# harp_analog_input_v1_0.net
KiCad netlist of a schematic drawn in EAGLE
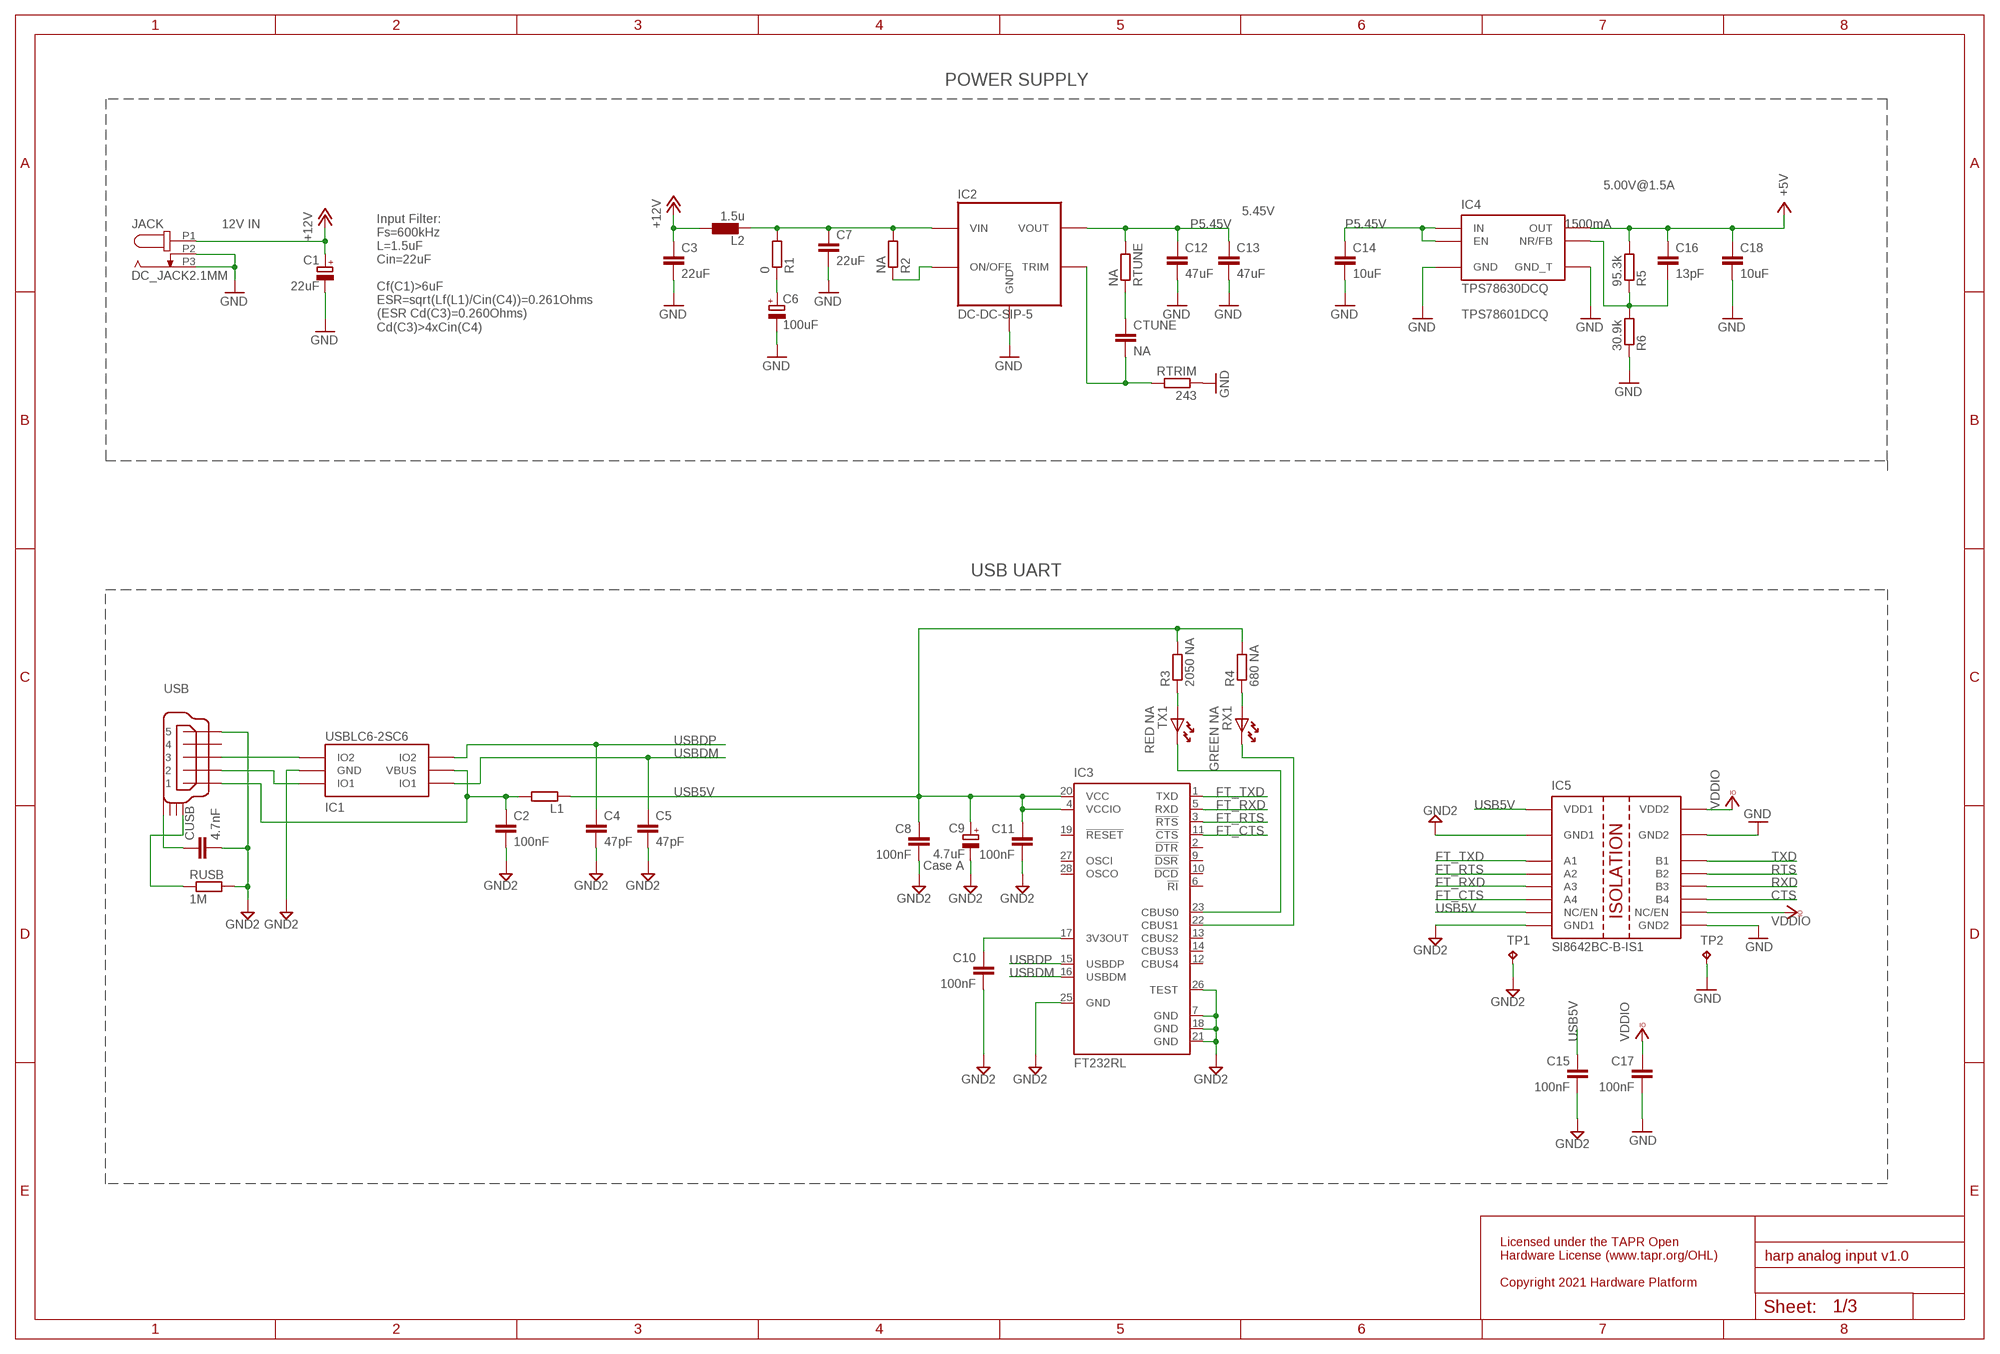
[diagram p0: schematic, sheet 1]
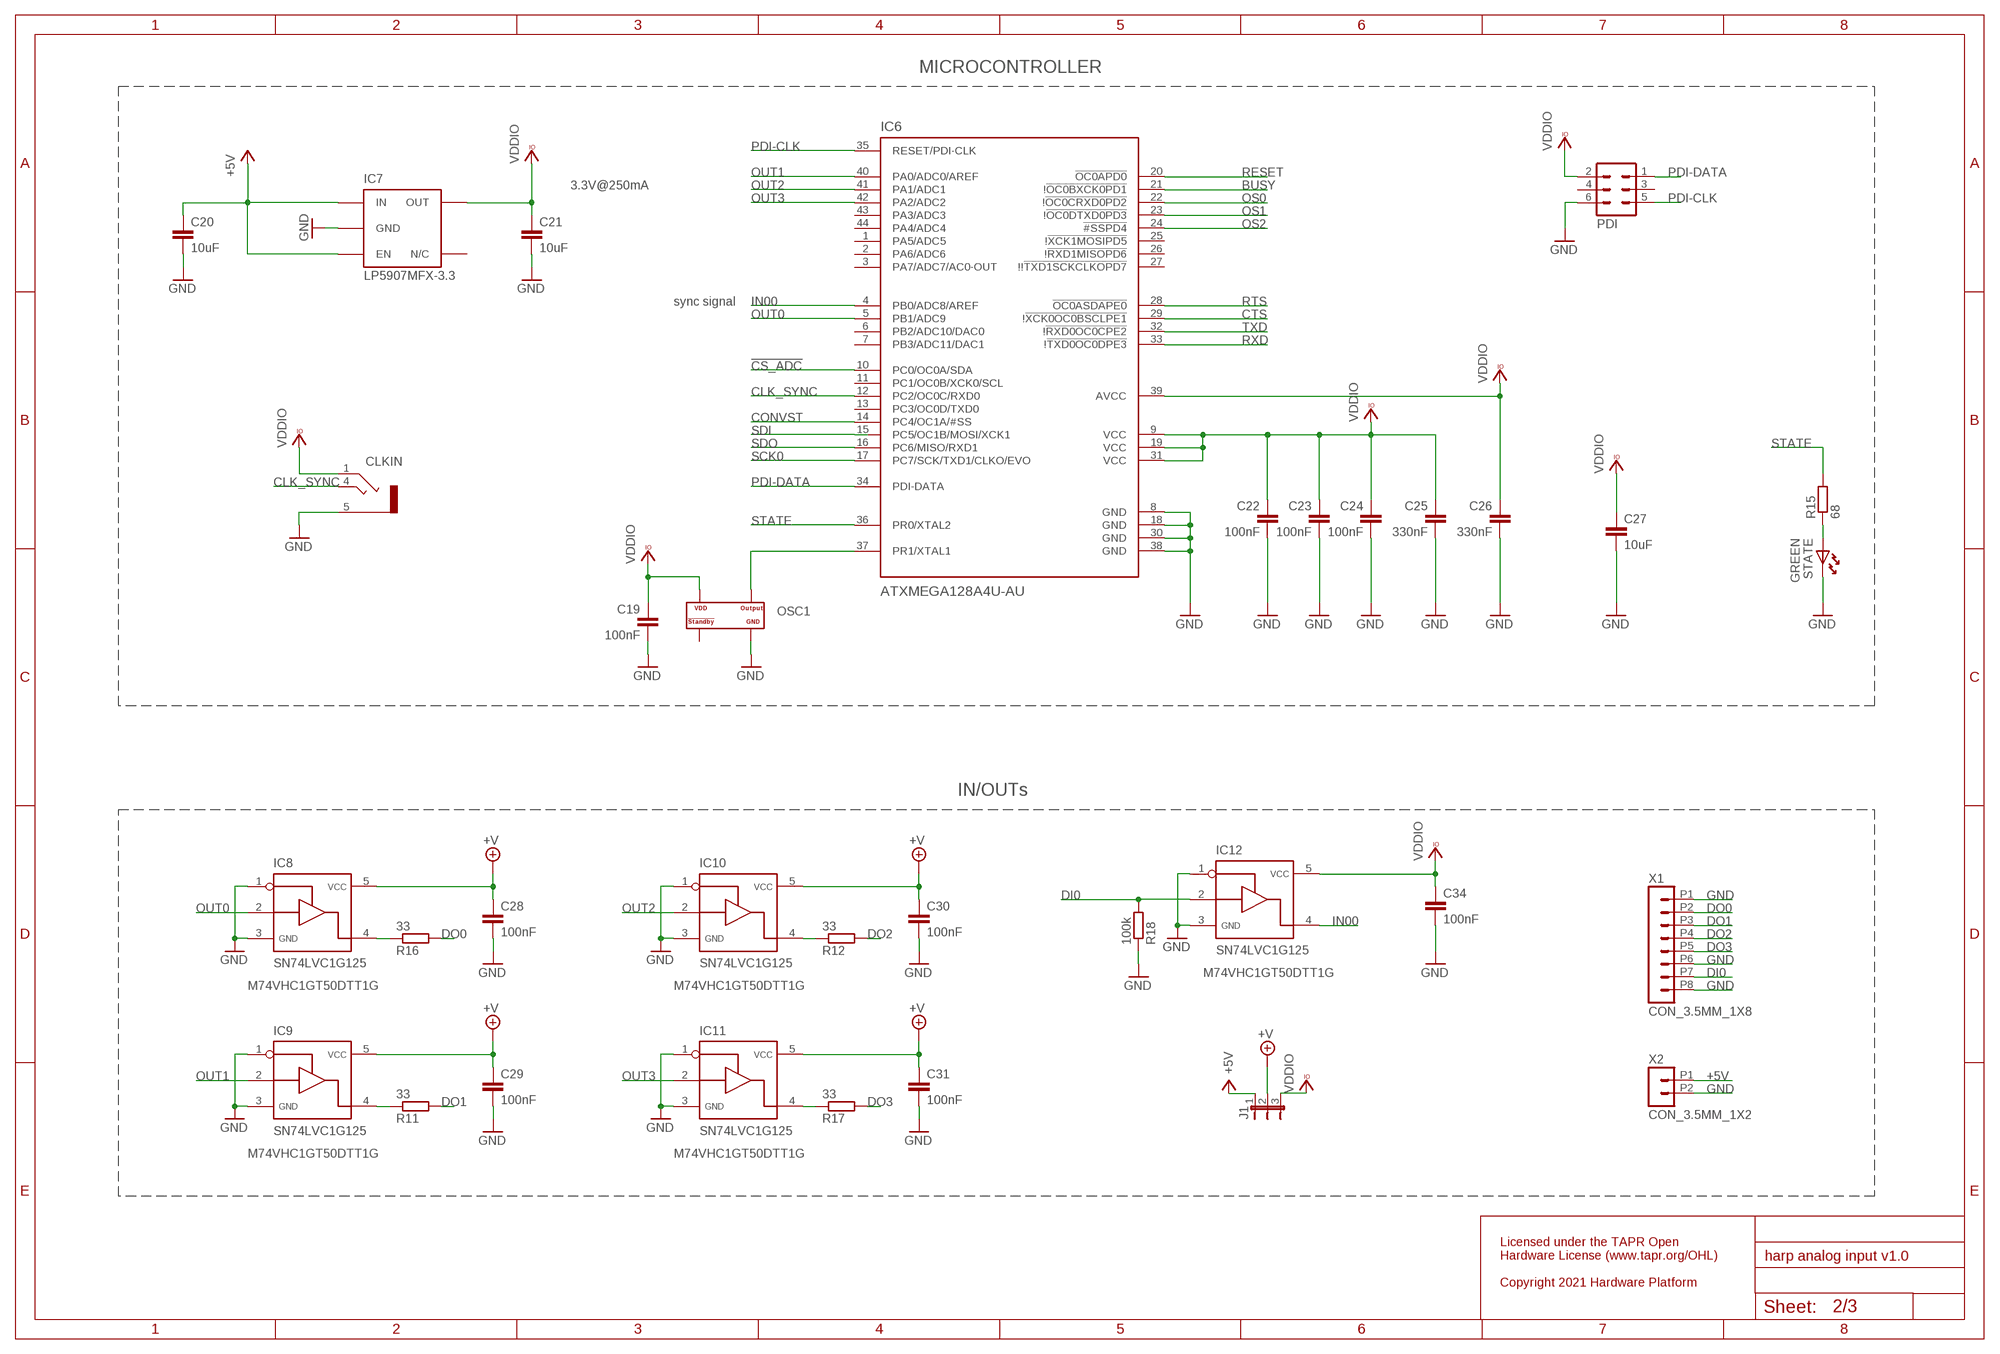
[diagram p1: schematic, sheet 2]
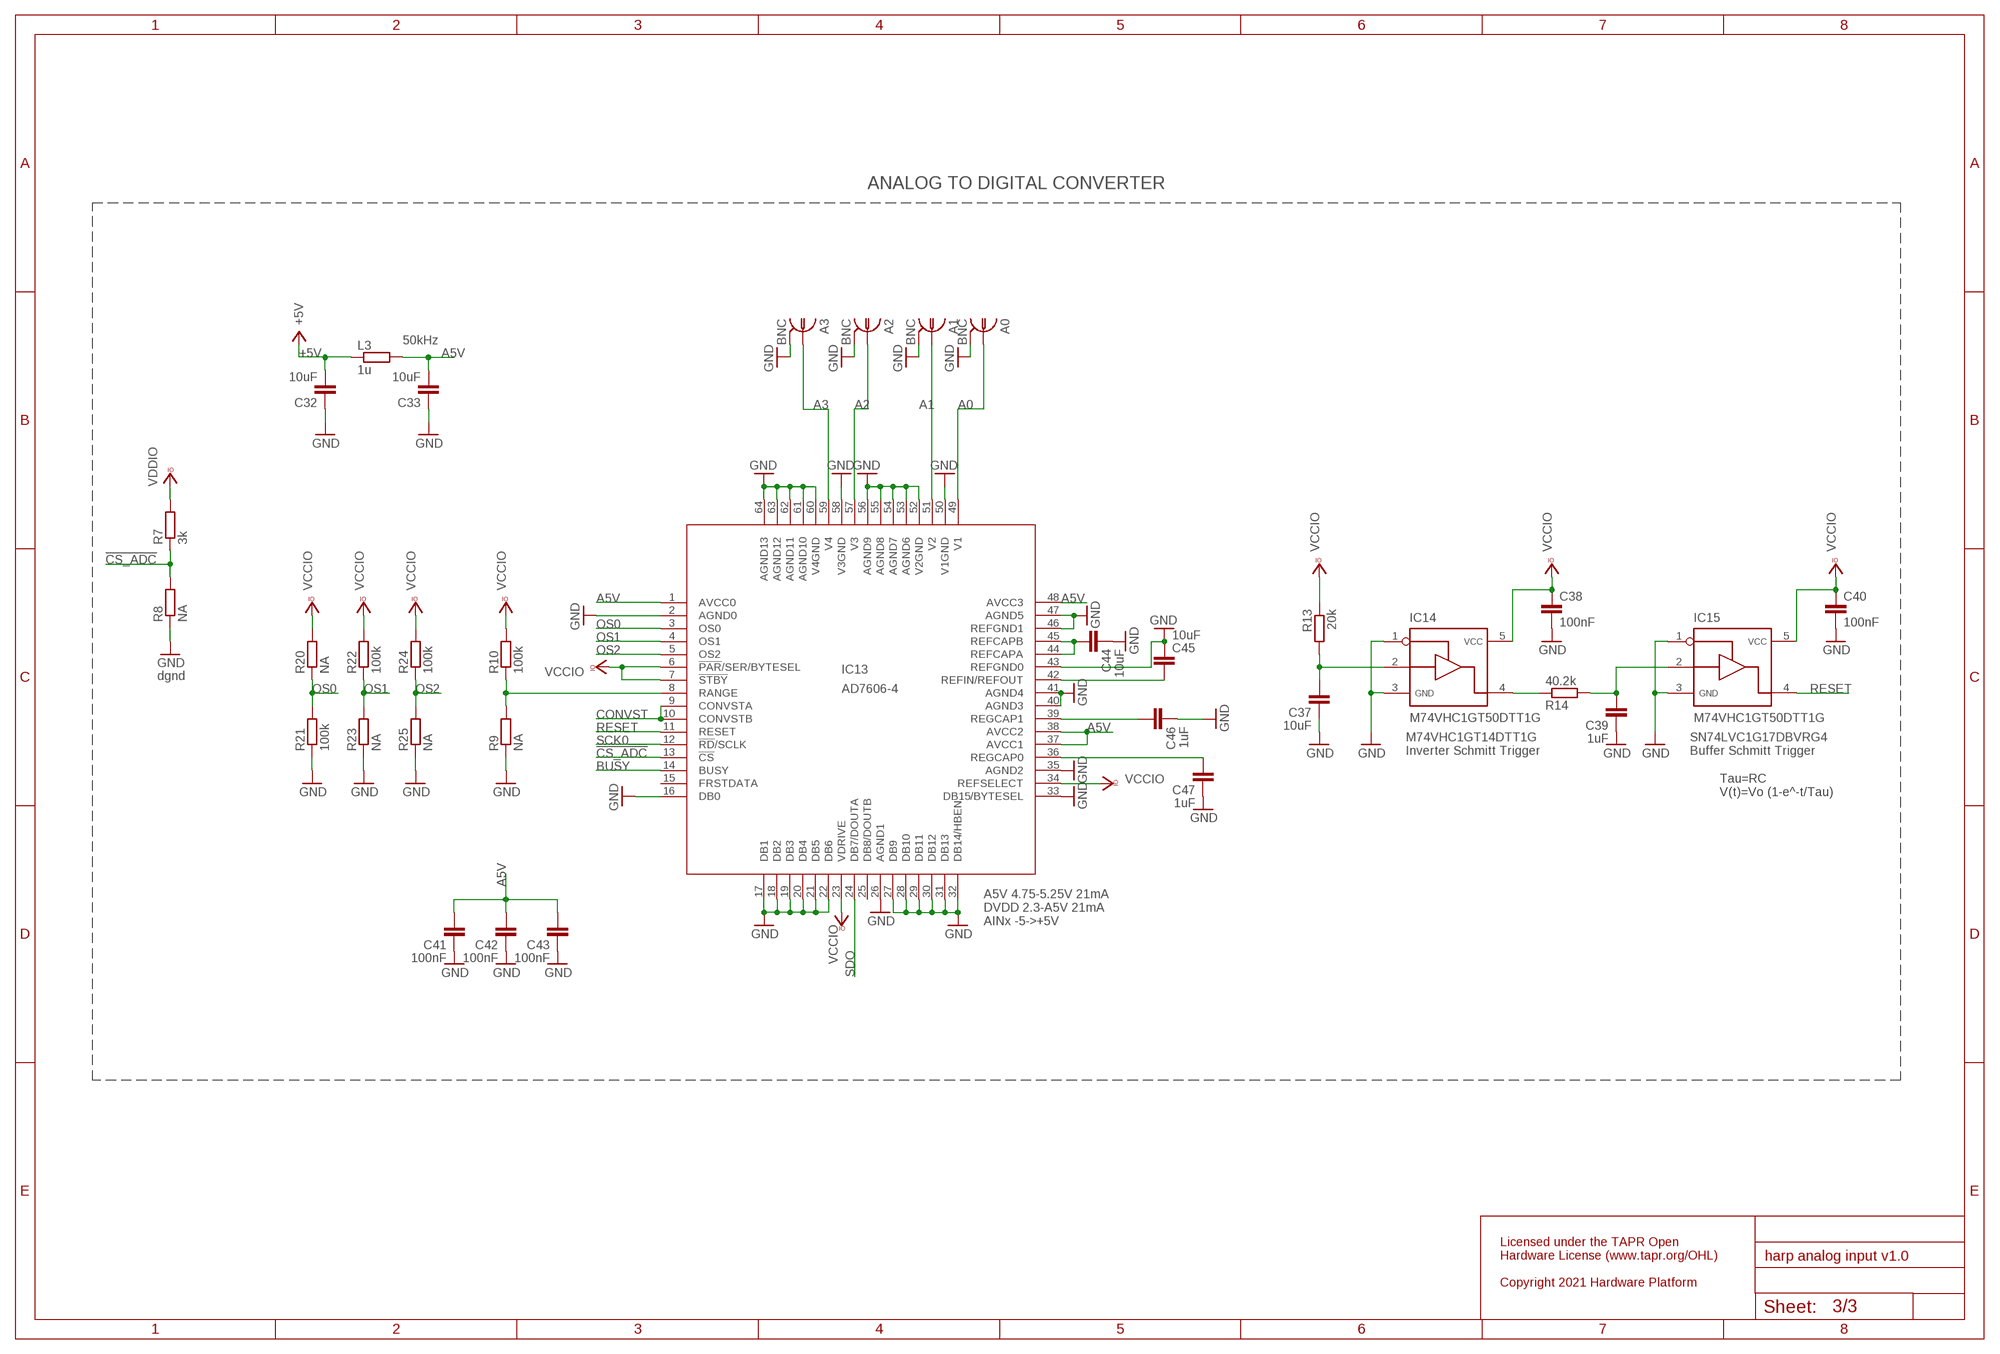
[diagram p2: schematic, sheet 3]

(export (version "E")
  (design (tool "Eeschema 10.0.6"))
  (components
    (comp (ref "A0")
      (value "BNC")
      (footprint "eagle-import:BNC_RA")
      (libsource (lib "eagle-import") (part "BNC"))
    )
    (comp (ref "A1")
      (value "BNC")
      (footprint "eagle-import:BNC_RA")
      (libsource (lib "eagle-import") (part "BNC"))
    )
    (comp (ref "A2")
      (value "BNC")
      (footprint "eagle-import:BNC_RA")
      (libsource (lib "eagle-import") (part "BNC"))
    )
    (comp (ref "A3")
      (value "BNC")
      (footprint "eagle-import:BNC_RA")
      (libsource (lib "eagle-import") (part "BNC"))
    )
    (comp (ref "C32")
      (value "10uF")
      (footprint "eagle-import:C0603")
      (libsource (lib "eagle-import") (part "C-EUC0603"))
    )
    (comp (ref "C33")
      (value "10uF")
      (footprint "eagle-import:C0603")
      (libsource (lib "eagle-import") (part "C-EUC0603"))
    )
    (comp (ref "C37")
      (value "10uF")
      (footprint "eagle-import:C0603")
      (libsource (lib "eagle-import") (part "C-EUC0603"))
    )
    (comp (ref "C38")
      (value "100nF")
      (footprint "eagle-import:C0402")
      (libsource (lib "eagle-import") (part "C-EUC0402"))
    )
    (comp (ref "C39")
      (value "1uF")
      (footprint "eagle-import:C0402")
      (libsource (lib "eagle-import") (part "C-EUC0402"))
    )
    (comp (ref "C40")
      (value "100nF")
      (footprint "eagle-import:C0402")
      (libsource (lib "eagle-import") (part "C-EUC0402"))
    )
    (comp (ref "C41")
      (value "100nF")
      (footprint "eagle-import:C0402")
      (libsource (lib "eagle-import") (part "C-EUC0402"))
    )
    (comp (ref "C42")
      (value "100nF")
      (footprint "eagle-import:C0402")
      (libsource (lib "eagle-import") (part "C-EUC0402"))
    )
    (comp (ref "C43")
      (value "100nF")
      (footprint "eagle-import:C0402")
      (libsource (lib "eagle-import") (part "C-EUC0402"))
    )
    (comp (ref "C44")
      (value "10uF")
      (footprint "eagle-import:C0603")
      (libsource (lib "eagle-import") (part "C-EUC0603"))
    )
    (comp (ref "C45")
      (value "10uF")
      (footprint "eagle-import:C0603")
      (libsource (lib "eagle-import") (part "C-EUC0603"))
    )
    (comp (ref "C46")
      (value "1uF")
      (footprint "eagle-import:C0402")
      (libsource (lib "eagle-import") (part "C-EUC0402"))
    )
    (comp (ref "C47")
      (value "1uF")
      (footprint "eagle-import:C0402")
      (libsource (lib "eagle-import") (part "C-EUC0402"))
    )
    (comp (ref "IC13")
      (value "AD7606-4")
      (footprint "eagle-import:LQFP-64")
      (libsource (lib "eagle-import") (part "AD7606-4"))
    )
    (comp (ref "IC14")
      (value "M74VHC1GT50DTT1G")
      (footprint "eagle-import:SOT23-5")
      (libsource (lib "eagle-import") (part "SN74LVC1G125"))
    )
    (comp (ref "IC15")
      (value "M74VHC1GT50DTT1G")
      (footprint "eagle-import:SOT23-5")
      (libsource (lib "eagle-import") (part "SN74LVC1G125"))
    )
    (comp (ref "L3")
      (value "1u")
      (footprint "eagle-import:R0402")
      (libsource (lib "eagle-import") (part "R-EU_R0402"))
    )
    (comp (ref "R7")
      (value "3k")
      (footprint "eagle-import:R0402")
      (libsource (lib "eagle-import") (part "R-EU_R0402"))
    )
    (comp (ref "R8")
      (value "NA")
      (footprint "eagle-import:R0402")
      (libsource (lib "eagle-import") (part "R-EU_R0402"))
    )
    (comp (ref "R9")
      (value "NA")
      (footprint "eagle-import:R0402")
      (libsource (lib "eagle-import") (part "R-EU_R0402"))
    )
    (comp (ref "R10")
      (value "100k")
      (footprint "eagle-import:R0402")
      (libsource (lib "eagle-import") (part "R-EU_R0402"))
    )
    (comp (ref "R13")
      (value "20k")
      (footprint "eagle-import:R0402")
      (libsource (lib "eagle-import") (part "R-EU_R0402"))
    )
    (comp (ref "R14")
      (value "40.2k")
      (footprint "eagle-import:R0402")
      (libsource (lib "eagle-import") (part "R-EU_R0402"))
    )
    (comp (ref "R20")
      (value "NA")
      (footprint "eagle-import:R0402")
      (libsource (lib "eagle-import") (part "R-EU_R0402"))
    )
    (comp (ref "R21")
      (value "100k")
      (footprint "eagle-import:R0402")
      (libsource (lib "eagle-import") (part "R-EU_R0402"))
    )
    (comp (ref "R22")
      (value "100k")
      (footprint "eagle-import:R0402")
      (libsource (lib "eagle-import") (part "R-EU_R0402"))
    )
    (comp (ref "R23")
      (value "NA")
      (footprint "eagle-import:R0402")
      (libsource (lib "eagle-import") (part "R-EU_R0402"))
    )
    (comp (ref "R24")
      (value "100k")
      (footprint "eagle-import:R0402")
      (libsource (lib "eagle-import") (part "R-EU_R0402"))
    )
    (comp (ref "R25")
      (value "NA")
      (footprint "eagle-import:R0402")
      (libsource (lib "eagle-import") (part "R-EU_R0402"))
    )
    (comp (ref "C1")
      (value "22uF")
      (footprint "eagle-import:CAP_100UF_HAND")
      (libsource (lib "eagle-import") (part "CAP_100UFHAND"))
    )
    (comp (ref "C2")
      (value "100nF")
      (footprint "eagle-import:C0402")
      (libsource (lib "eagle-import") (part "C-EUC0402"))
    )
    (comp (ref "C3")
      (value "22uF")
      (footprint "eagle-import:C1210")
      (libsource (lib "eagle-import") (part "C-EUC1210"))
    )
    (comp (ref "C4")
      (value "47pF")
      (footprint "eagle-import:C0402")
      (libsource (lib "eagle-import") (part "C-EUC0402"))
    )
    (comp (ref "C5")
      (value "47pF")
      (footprint "eagle-import:C0402")
      (libsource (lib "eagle-import") (part "C-EUC0402"))
    )
    (comp (ref "C6")
      (value "100uF")
      (footprint "eagle-import:PANASONIC_E")
      (libsource (lib "eagle-import") (part "CPOL-EUE"))
    )
    (comp (ref "C7")
      (value "22uF")
      (footprint "eagle-import:C1210")
      (libsource (lib "eagle-import") (part "C-EUC1210"))
    )
    (comp (ref "C8")
      (value "100nF")
      (footprint "eagle-import:C0402")
      (libsource (lib "eagle-import") (part "C-EUC0402"))
    )
    (comp (ref "C9")
      (value "4.7uF")
      (footprint "eagle-import:A_3216-18W")
      (libsource (lib "eagle-import") (part "CPOL-EUA/3216-18W"))
    )
    (comp (ref "C10")
      (value "100nF")
      (footprint "eagle-import:C0402")
      (libsource (lib "eagle-import") (part "C-EUC0402"))
    )
    (comp (ref "C11")
      (value "100nF")
      (footprint "eagle-import:C0402")
      (libsource (lib "eagle-import") (part "C-EUC0402"))
    )
    (comp (ref "C12")
      (value "47uF")
      (footprint "eagle-import:C1210")
      (libsource (lib "eagle-import") (part "C-EUC1210"))
    )
    (comp (ref "C13")
      (value "47uF")
      (footprint "eagle-import:C1210")
      (libsource (lib "eagle-import") (part "C-EUC1210"))
    )
    (comp (ref "C14")
      (value "10uF")
      (footprint "eagle-import:C0603")
      (libsource (lib "eagle-import") (part "C-EUC0603"))
    )
    (comp (ref "C15")
      (value "100nF")
      (footprint "eagle-import:C0402")
      (libsource (lib "eagle-import") (part "C-EUC0402"))
    )
    (comp (ref "C16")
      (value "13pF")
      (footprint "eagle-import:C0402")
      (libsource (lib "eagle-import") (part "C-EUC0402"))
    )
    (comp (ref "C17")
      (value "100nF")
      (footprint "eagle-import:C0402")
      (libsource (lib "eagle-import") (part "C-EUC0402"))
    )
    (comp (ref "C18")
      (value "10uF")
      (footprint "eagle-import:C0603")
      (libsource (lib "eagle-import") (part "C-EUC0603"))
    )
    (comp (ref "CTUNE")
      (value "NA")
      (footprint "eagle-import:C0402")
      (libsource (lib "eagle-import") (part "C-EUC0402"))
    )
    (comp (ref "CUSB")
      (value "4.7nF")
      (footprint "eagle-import:C0402")
      (libsource (lib "eagle-import") (part "C-EUC0402"))
    )
    (comp (ref "IC1")
      (value "USBLC6-2SC6")
      (footprint "eagle-import:SOT23-6L")
      (libsource (lib "eagle-import") (part "USBLC6-2"))
    )
    (comp (ref "IC2")
      (value "DC-DC-SIP-5")
      (footprint "eagle-import:SIP-5")
      (libsource (lib "eagle-import") (part "DC-DC-SIP-5"))
    )
    (comp (ref "IC3")
      (value "FT232RL")
      (footprint "eagle-import:SSOP28")
      (libsource (lib "eagle-import") (part "FT232RL"))
    )
    (comp (ref "IC4")
      (value "TPS78630DCQ")
      (footprint "eagle-import:SOT223-6")
      (libsource (lib "eagle-import") (part "TPS795XX"))
    )
    (comp (ref "IC5")
      (value "SI8642BC-B-IS1")
      (footprint "eagle-import:NSOIC-16")
      (libsource (lib "eagle-import") (part "SI8645"))
    )
    (comp (ref "JACK")
      (value "DC_JACK2.1MM")
      (footprint "eagle-import:DC_POWER_INPUT_2.1MM")
      (libsource (lib "eagle-import") (part "DC_JACK2.1MM"))
    )
    (comp (ref "L1")
      (value "???")
      (footprint "eagle-import:R0805")
      (libsource (lib "eagle-import") (part "R-EU_R0805"))
    )
    (comp (ref "L2")
      (value "1.5u")
      (footprint "eagle-import:IND_LPS4012")
      (libsource (lib "eagle-import") (part "INDLPS4012"))
    )
    (comp (ref "R1")
      (value "0")
      (footprint "eagle-import:R0402")
      (libsource (lib "eagle-import") (part "R-EU_R0402"))
    )
    (comp (ref "R2")
      (value "NA")
      (footprint "eagle-import:R0402")
      (libsource (lib "eagle-import") (part "R-EU_R0402"))
    )
    (comp (ref "R3")
      (value "2050 NA")
      (footprint "eagle-import:R0402")
      (libsource (lib "eagle-import") (part "R-EU_R0402"))
    )
    (comp (ref "R4")
      (value "680 NA")
      (footprint "eagle-import:R0402")
      (libsource (lib "eagle-import") (part "R-EU_R0402"))
    )
    (comp (ref "R5")
      (value "95.3k")
      (footprint "eagle-import:R0402")
      (libsource (lib "eagle-import") (part "R-EU_R0402"))
    )
    (comp (ref "R6")
      (value "30.9k")
      (footprint "eagle-import:R0402")
      (libsource (lib "eagle-import") (part "R-EU_R0402"))
    )
    (comp (ref "RTRIM")
      (value "243")
      (footprint "eagle-import:R0402")
      (libsource (lib "eagle-import") (part "R-EU_R0402"))
    )
    (comp (ref "RTUNE")
      (value "NA")
      (footprint "eagle-import:R0402")
      (libsource (lib "eagle-import") (part "R-EU_R0402"))
    )
    (comp (ref "RUSB")
      (value "1M")
      (footprint "eagle-import:R0402")
      (libsource (lib "eagle-import") (part "R-EU_R0402"))
    )
    (comp (ref "RX1")
      (value "GREEN NA")
      (footprint "eagle-import:LED_HAND")
      (libsource (lib "eagle-import") (part "LEDHAND"))
    )
    (comp (ref "TP1")
      (value "TPTP08SQ")
      (footprint "eagle-import:TP08SQ")
      (libsource (lib "eagle-import") (part "TPTP08SQ"))
    )
    (comp (ref "TP2")
      (value "TPTP08SQ")
      (footprint "eagle-import:TP08SQ")
      (libsource (lib "eagle-import") (part "TPTP08SQ"))
    )
    (comp (ref "TX1")
      (value "RED NA")
      (footprint "eagle-import:LED_HAND")
      (libsource (lib "eagle-import") (part "LEDHAND"))
    )
    (comp (ref "USB")
      (value "USB_MINI_B")
      (footprint "eagle-import:240-0002-1")
      (libsource (lib "eagle-import") (part "USB_MINI_B"))
    )
    (comp (ref "C19")
      (value "100nF")
      (footprint "eagle-import:C0402")
      (libsource (lib "eagle-import") (part "C-EUC0402"))
    )
    (comp (ref "C20")
      (value "10uF")
      (footprint "eagle-import:C0603")
      (libsource (lib "eagle-import") (part "C-EUC0603"))
    )
    (comp (ref "C21")
      (value "10uF")
      (footprint "eagle-import:C0603")
      (libsource (lib "eagle-import") (part "C-EUC0603"))
    )
    (comp (ref "C22")
      (value "100nF")
      (footprint "eagle-import:C0402")
      (libsource (lib "eagle-import") (part "C-EUC0402"))
    )
    (comp (ref "C23")
      (value "100nF")
      (footprint "eagle-import:C0402")
      (libsource (lib "eagle-import") (part "C-EUC0402"))
    )
    (comp (ref "C24")
      (value "100nF")
      (footprint "eagle-import:C0402")
      (libsource (lib "eagle-import") (part "C-EUC0402"))
    )
    (comp (ref "C25")
      (value "330nF")
      (footprint "eagle-import:C0402")
      (libsource (lib "eagle-import") (part "C-EUC0402"))
    )
    (comp (ref "C26")
      (value "330nF")
      (footprint "eagle-import:C0402")
      (libsource (lib "eagle-import") (part "C-EUC0402"))
    )
    (comp (ref "C27")
      (value "10uF")
      (footprint "eagle-import:C0603")
      (libsource (lib "eagle-import") (part "C-EUC0603"))
    )
    (comp (ref "C28")
      (value "100nF")
      (footprint "eagle-import:C0402")
      (libsource (lib "eagle-import") (part "C-EUC0402"))
    )
    (comp (ref "C29")
      (value "100nF")
      (footprint "eagle-import:C0402")
      (libsource (lib "eagle-import") (part "C-EUC0402"))
    )
    (comp (ref "C30")
      (value "100nF")
      (footprint "eagle-import:C0402")
      (libsource (lib "eagle-import") (part "C-EUC0402"))
    )
    (comp (ref "C31")
      (value "100nF")
      (footprint "eagle-import:C0402")
      (libsource (lib "eagle-import") (part "C-EUC0402"))
    )
    (comp (ref "C34")
      (value "100nF")
      (footprint "eagle-import:C0402")
      (libsource (lib "eagle-import") (part "C-EUC0402"))
    )
    (comp (ref "CLKIN")
      (value "STEREO_JACK")
      (footprint "eagle-import:35RASMT2BHNTRX")
      (libsource (lib "eagle-import") (part "STEREO_JACK"))
    )
    (comp (ref "IC6")
      (value "ATXMEGA128A4U-AU")
      (footprint "eagle-import:QFP80P1200X1200X120-44N")
      (libsource (lib "eagle-import") (part "AT-XMEGA-XXA4-AU"))
    )
    (comp (ref "IC7")
      (value "LP5907MFX-3.3")
      (footprint "eagle-import:TSOT23-5")
      (libsource (lib "eagle-import") (part "TLV700XX"))
    )
    (comp (ref "IC8")
      (value "SN74LVC1G125")
      (footprint "eagle-import:SOT23-5")
      (libsource (lib "eagle-import") (part "SN74LVC1G125"))
    )
    (comp (ref "IC9")
      (value "SN74LVC1G125")
      (footprint "eagle-import:SOT23-5")
      (libsource (lib "eagle-import") (part "SN74LVC1G125"))
    )
    (comp (ref "IC10")
      (value "SN74LVC1G125")
      (footprint "eagle-import:SOT23-5")
      (libsource (lib "eagle-import") (part "SN74LVC1G125"))
    )
    (comp (ref "IC11")
      (value "SN74LVC1G125")
      (footprint "eagle-import:SOT23-5")
      (libsource (lib "eagle-import") (part "SN74LVC1G125"))
    )
    (comp (ref "IC12")
      (value "SN74LVC1G125")
      (footprint "eagle-import:SOT23-5")
      (libsource (lib "eagle-import") (part "SN74LVC1G125"))
    )
    (comp (ref "J1")
      (value "JP2E")
      (footprint "eagle-import:JP2")
      (libsource (lib "eagle-import") (part "JP2E"))
    )
    (comp (ref "OSC1")
      (value "OSCILLATOR")
      (footprint "eagle-import:OSCILLATOR_3.2X2.5")
      (libsource (lib "eagle-import") (part "OSCILLATOR"))
    )
    (comp (ref "PDI")
      (value "MA03-2")
      (footprint "eagle-import:MA03-2")
      (libsource (lib "eagle-import") (part "MA03-2"))
    )
    (comp (ref "R11")
      (value "33")
      (footprint "eagle-import:R0402")
      (libsource (lib "eagle-import") (part "R-EU_R0402"))
    )
    (comp (ref "R12")
      (value "33")
      (footprint "eagle-import:R0402")
      (libsource (lib "eagle-import") (part "R-EU_R0402"))
    )
    (comp (ref "R15")
      (value "68")
      (footprint "eagle-import:R0402")
      (libsource (lib "eagle-import") (part "R-EU_R0402"))
    )
    (comp (ref "R16")
      (value "33")
      (footprint "eagle-import:R0402")
      (libsource (lib "eagle-import") (part "R-EU_R0402"))
    )
    (comp (ref "R17")
      (value "33")
      (footprint "eagle-import:R0402")
      (libsource (lib "eagle-import") (part "R-EU_R0402"))
    )
    (comp (ref "R18")
      (value "100k")
      (footprint "eagle-import:R0402")
      (libsource (lib "eagle-import") (part "R-EU_R0402"))
    )
    (comp (ref "STATE")
      (value "GREEN")
      (footprint "eagle-import:LED_HAND")
      (libsource (lib "eagle-import") (part "LEDHAND"))
    )
    (comp (ref "X1")
      (value "CON_3.5MM_1X8")
      (footprint "eagle-import:CON_3.5MM_1X8")
      (libsource (lib "eagle-import") (part "CON_3.5MM_1X8"))
    )
    (comp (ref "X2")
      (value "CON_3.5MM_1X2")
      (footprint "eagle-import:CON_3.5MM_1X2")
      (libsource (lib "eagle-import") (part "CON_3.5MM_1X2"))
    )
  )
  (nets
    (net (code "1") (name "+5V") (class "Default")
      (node (ref "C16") (pin "1") (pinfunction "1_1") (pintype "passive"))
      (node (ref "C18") (pin "1") (pinfunction "1_1") (pintype "passive"))
      (node (ref "C20") (pin "1") (pinfunction "1_1") (pintype "passive"))
      (node (ref "C32") (pin "2") (pinfunction "2_2") (pintype "passive"))
      (node (ref "IC4") (pin "P$4") (pinfunction "OUT_P$4") (pintype "bidirectional"))
      (node (ref "IC7") (pin "1") (pinfunction "IN_1") (pintype "bidirectional"))
      (node (ref "IC7") (pin "3") (pinfunction "EN_3") (pintype "bidirectional"))
      (node (ref "J1") (pin "1") (pinfunction "1_1") (pintype "passive"))
      (node (ref "L3") (pin "1") (pinfunction "1_1") (pintype "passive"))
      (node (ref "R5") (pin "2") (pinfunction "2_2") (pintype "passive"))
      (node (ref "X2") (pin "P1") (pinfunction "1_P1") (pintype "passive"))
    )
    (net (code "2") (name "+12V") (class "Default")
      (node (ref "C1") (pin "+") (pinfunction "+_+") (pintype "passive"))
      (node (ref "C3") (pin "1") (pinfunction "1_1") (pintype "passive"))
      (node (ref "JACK") (pin "P1") (pinfunction "1_P1") (pintype "passive"))
      (node (ref "L2") (pin "1") (pinfunction "1_1") (pintype "passive"))
    )
    (net (code "3") (name "+V") (class "Default")
      (node (ref "C28") (pin "1") (pinfunction "1_1") (pintype "passive"))
      (node (ref "C29") (pin "1") (pinfunction "1_1") (pintype "passive"))
      (node (ref "C30") (pin "1") (pinfunction "1_1") (pintype "passive"))
      (node (ref "C31") (pin "1") (pinfunction "1_1") (pintype "passive"))
      (node (ref "IC10") (pin "5") (pinfunction "P$5_5") (pintype "bidirectional"))
      (node (ref "IC11") (pin "5") (pinfunction "P$5_5") (pintype "bidirectional"))
      (node (ref "IC8") (pin "5") (pinfunction "P$5_5") (pintype "bidirectional"))
      (node (ref "IC9") (pin "5") (pinfunction "P$5_5") (pintype "bidirectional"))
      (node (ref "J1") (pin "2") (pinfunction "2_2") (pintype "passive"))
    )
    (net (code "4") (name "A0") (class "Default")
      (node (ref "A0") (pin "1") (pinfunction "1_1") (pintype "passive"))
      (node (ref "IC13") (pin "49") (pinfunction "V1_49") (pintype "bidirectional"))
    )
    (net (code "5") (name "A1") (class "Default")
      (node (ref "A1") (pin "1") (pinfunction "1_1") (pintype "passive"))
      (node (ref "IC13") (pin "51") (pinfunction "V2_51") (pintype "bidirectional"))
    )
    (net (code "6") (name "A2") (class "Default")
      (node (ref "A2") (pin "1") (pinfunction "1_1") (pintype "passive"))
      (node (ref "IC13") (pin "57") (pinfunction "V3_57") (pintype "bidirectional"))
    )
    (net (code "7") (name "A3") (class "Default")
      (node (ref "A3") (pin "1") (pinfunction "1_1") (pintype "passive"))
      (node (ref "IC13") (pin "59") (pinfunction "V4_59") (pintype "bidirectional"))
    )
    (net (code "8") (name "A5V") (class "Default")
      (node (ref "C33") (pin "2") (pinfunction "2_2") (pintype "passive"))
      (node (ref "C41") (pin "2") (pinfunction "2_2") (pintype "passive"))
      (node (ref "C42") (pin "2") (pinfunction "2_2") (pintype "passive"))
      (node (ref "C43") (pin "2") (pinfunction "2_2") (pintype "passive"))
      (node (ref "IC13") (pin "1") (pinfunction "AVCC0_1") (pintype "bidirectional"))
      (node (ref "IC13") (pin "37") (pinfunction "AVCC1_37") (pintype "bidirectional"))
      (node (ref "IC13") (pin "38") (pinfunction "AVCC2_38") (pintype "bidirectional"))
      (node (ref "IC13") (pin "48") (pinfunction "AVCC3_48") (pintype "bidirectional"))
      (node (ref "L3") (pin "2") (pinfunction "2_2") (pintype "passive"))
    )
    (net (code "9") (name "BUSY") (class "Default")
      (node (ref "IC13") (pin "14") (pinfunction "BUSY_14") (pintype "bidirectional"))
      (node (ref "IC6") (pin "21") (pinfunction "~OC0BXCK0PD1_21") (pintype "bidirectional"))
    )
    (net (code "10") (name "CLK_SYNC") (class "Default")
      (node (ref "CLKIN") (pin "4") (pinfunction "4_4") (pintype "passive"))
      (node (ref "IC6") (pin "12") (pinfunction "PC2/OC0C/RXD0_12") (pintype "bidirectional"))
    )
    (net (code "11") (name "CONVST") (class "Default")
      (node (ref "IC13") (pin "10") (pinfunction "CONVSTB_10") (pintype "bidirectional"))
      (node (ref "IC13") (pin "9") (pinfunction "CONVSTA_9") (pintype "bidirectional"))
      (node (ref "IC6") (pin "14") (pinfunction "PC4/OC1A/#SS_14") (pintype "bidirectional"))
    )
    (net (code "12") (name "CTS") (class "Default")
      (node (ref "IC5") (pin "11") (pinfunction "B4_11") (pintype "bidirectional"))
      (node (ref "IC6") (pin "29") (pinfunction "~XCK0OC0BSCLPE1_29") (pintype "bidirectional"))
    )
    (net (code "13") (name "DI0") (class "Default")
      (node (ref "IC12") (pin "2") (pinfunction "P$2_2") (pintype "bidirectional"))
      (node (ref "R18") (pin "2") (pinfunction "2_2") (pintype "passive"))
      (node (ref "X1") (pin "P7") (pinfunction "7_P7") (pintype "passive"))
    )
    (net (code "14") (name "DO0") (class "Default")
      (node (ref "R16") (pin "2") (pinfunction "2_2") (pintype "passive"))
      (node (ref "X1") (pin "P2") (pinfunction "2_P2") (pintype "passive"))
    )
    (net (code "15") (name "DO1") (class "Default")
      (node (ref "R11") (pin "2") (pinfunction "2_2") (pintype "passive"))
      (node (ref "X1") (pin "P3") (pinfunction "3_P3") (pintype "passive"))
    )
    (net (code "16") (name "DO2") (class "Default")
      (node (ref "R12") (pin "2") (pinfunction "2_2") (pintype "passive"))
      (node (ref "X1") (pin "P4") (pinfunction "4_P4") (pintype "passive"))
    )
    (net (code "17") (name "DO3") (class "Default")
      (node (ref "R17") (pin "2") (pinfunction "2_2") (pintype "passive"))
      (node (ref "X1") (pin "P5") (pinfunction "5_P5") (pintype "passive"))
    )
    (net (code "18") (name "FT_CTS") (class "Default")
      (node (ref "IC3") (pin "11") (pinfunction "~{CTS}_11") (pintype "input"))
      (node (ref "IC5") (pin "6") (pinfunction "A4_6") (pintype "bidirectional"))
    )
    (net (code "19") (name "FT_RTS") (class "Default")
      (node (ref "IC3") (pin "3") (pinfunction "~{RTS}_3") (pintype "output"))
      (node (ref "IC5") (pin "4") (pinfunction "A2_4") (pintype "bidirectional"))
    )
    (net (code "20") (name "FT_RXD") (class "Default")
      (node (ref "IC3") (pin "5") (pinfunction "RXD_5") (pintype "input"))
      (node (ref "IC5") (pin "5") (pinfunction "A3_5") (pintype "bidirectional"))
    )
    (net (code "21") (name "FT_TXD") (class "Default")
      (node (ref "IC3") (pin "1") (pinfunction "TXD_1") (pintype "output"))
      (node (ref "IC5") (pin "3") (pinfunction "A1_3") (pintype "bidirectional"))
    )
    (net (code "22") (name "GND") (class "Default")
      (node (ref "A0") (pin "2") (pinfunction "2_2") (pintype "passive"))
      (node (ref "A1") (pin "2") (pinfunction "2_2") (pintype "passive"))
      (node (ref "A2") (pin "2") (pinfunction "2_2") (pintype "passive"))
      (node (ref "A3") (pin "2") (pinfunction "2_2") (pintype "passive"))
      (node (ref "C1") (pin "-") (pinfunction "-_-") (pintype "passive"))
      (node (ref "C12") (pin "2") (pinfunction "2_2") (pintype "passive"))
      (node (ref "C13") (pin "2") (pinfunction "2_2") (pintype "passive"))
      (node (ref "C14") (pin "2") (pinfunction "2_2") (pintype "passive"))
      (node (ref "C17") (pin "2") (pinfunction "2_2") (pintype "passive"))
      (node (ref "C18") (pin "2") (pinfunction "2_2") (pintype "passive"))
      (node (ref "C19") (pin "2") (pinfunction "2_2") (pintype "passive"))
      (node (ref "C20") (pin "2") (pinfunction "2_2") (pintype "passive"))
      (node (ref "C21") (pin "2") (pinfunction "2_2") (pintype "passive"))
      (node (ref "C22") (pin "2") (pinfunction "2_2") (pintype "passive"))
      (node (ref "C23") (pin "2") (pinfunction "2_2") (pintype "passive"))
      (node (ref "C24") (pin "2") (pinfunction "2_2") (pintype "passive"))
      (node (ref "C25") (pin "2") (pinfunction "2_2") (pintype "passive"))
      (node (ref "C26") (pin "2") (pinfunction "2_2") (pintype "passive"))
      (node (ref "C27") (pin "2") (pinfunction "2_2") (pintype "passive"))
      (node (ref "C28") (pin "2") (pinfunction "2_2") (pintype "passive"))
      (node (ref "C29") (pin "2") (pinfunction "2_2") (pintype "passive"))
      (node (ref "C3") (pin "2") (pinfunction "2_2") (pintype "passive"))
      (node (ref "C30") (pin "2") (pinfunction "2_2") (pintype "passive"))
      (node (ref "C31") (pin "2") (pinfunction "2_2") (pintype "passive"))
      (node (ref "C32") (pin "1") (pinfunction "1_1") (pintype "passive"))
      (node (ref "C33") (pin "1") (pinfunction "1_1") (pintype "passive"))
      (node (ref "C34") (pin "2") (pinfunction "2_2") (pintype "passive"))
      (node (ref "C37") (pin "1") (pinfunction "1_1") (pintype "passive"))
      (node (ref "C38") (pin "2") (pinfunction "2_2") (pintype "passive"))
      (node (ref "C39") (pin "1") (pinfunction "1_1") (pintype "passive"))
      (node (ref "C40") (pin "2") (pinfunction "2_2") (pintype "passive"))
      (node (ref "C41") (pin "1") (pinfunction "1_1") (pintype "passive"))
      (node (ref "C42") (pin "1") (pinfunction "1_1") (pintype "passive"))
      (node (ref "C43") (pin "1") (pinfunction "1_1") (pintype "passive"))
      (node (ref "C44") (pin "1") (pinfunction "1_1") (pintype "passive"))
      (node (ref "C45") (pin "1") (pinfunction "1_1") (pintype "passive"))
      (node (ref "C46") (pin "1") (pinfunction "1_1") (pintype "passive"))
      (node (ref "C47") (pin "1") (pinfunction "1_1") (pintype "passive"))
      (node (ref "C6") (pin "-") (pinfunction "-_-") (pintype "passive"))
      (node (ref "C7") (pin "2") (pinfunction "2_2") (pintype "passive"))
      (node (ref "CLKIN") (pin "5") (pinfunction "5_5") (pintype "passive"))
      (node (ref "IC10") (pin "1") (pinfunction "P$1_1") (pintype "bidirectional"))
      (node (ref "IC10") (pin "3") (pinfunction "P$3_3") (pintype "bidirectional"))
      (node (ref "IC11") (pin "1") (pinfunction "P$1_1") (pintype "bidirectional"))
      (node (ref "IC11") (pin "3") (pinfunction "P$3_3") (pintype "bidirectional"))
      (node (ref "IC12") (pin "1") (pinfunction "P$1_1") (pintype "bidirectional"))
      (node (ref "IC12") (pin "3") (pinfunction "P$3_3") (pintype "bidirectional"))
      (node (ref "IC13") (pin "16") (pinfunction "DB0_16") (pintype "bidirectional"))
      (node (ref "IC13") (pin "17") (pinfunction "DB1_17") (pintype "bidirectional"))
      (node (ref "IC13") (pin "18") (pinfunction "DB2_18") (pintype "bidirectional"))
      (node (ref "IC13") (pin "19") (pinfunction "DB3_19") (pintype "bidirectional"))
      (node (ref "IC13") (pin "2") (pinfunction "AGND0_2") (pintype "bidirectional"))
      (node (ref "IC13") (pin "20") (pinfunction "DB4_20") (pintype "bidirectional"))
      (node (ref "IC13") (pin "21") (pinfunction "DB5_21") (pintype "bidirectional"))
      (node (ref "IC13") (pin "22") (pinfunction "DB6_22") (pintype "bidirectional"))
      (node (ref "IC13") (pin "26") (pinfunction "AGND1_26") (pintype "bidirectional"))
      (node (ref "IC13") (pin "27") (pinfunction "DB9_27") (pintype "bidirectional"))
      (node (ref "IC13") (pin "28") (pinfunction "DB10_28") (pintype "bidirectional"))
      (node (ref "IC13") (pin "29") (pinfunction "DB11_29") (pintype "input"))
      (node (ref "IC13") (pin "30") (pinfunction "DB12_30") (pintype "bidirectional"))
      (node (ref "IC13") (pin "31") (pinfunction "DB13_31") (pintype "bidirectional"))
      (node (ref "IC13") (pin "32") (pinfunction "DB14/HBEN_32") (pintype "bidirectional"))
      (node (ref "IC13") (pin "33") (pinfunction "DB15/BYTESEL_33") (pintype "bidirectional"))
      (node (ref "IC13") (pin "35") (pinfunction "AGND2_35") (pintype "bidirectional"))
      (node (ref "IC13") (pin "40") (pinfunction "AGND3_40") (pintype "bidirectional"))
      (node (ref "IC13") (pin "41") (pinfunction "AGND4_41") (pintype "bidirectional"))
      (node (ref "IC13") (pin "43") (pinfunction "REFGND0_43") (pintype "bidirectional"))
      (node (ref "IC13") (pin "46") (pinfunction "REFGND1_46") (pintype "bidirectional"))
      (node (ref "IC13") (pin "47") (pinfunction "AGND5_47") (pintype "bidirectional"))
      (node (ref "IC13") (pin "50") (pinfunction "V1GND_50") (pintype "bidirectional"))
      (node (ref "IC13") (pin "52") (pinfunction "V2GND_52") (pintype "bidirectional"))
      (node (ref "IC13") (pin "53") (pinfunction "AGND6_53") (pintype "bidirectional"))
      (node (ref "IC13") (pin "54") (pinfunction "AGND7_54") (pintype "bidirectional"))
      (node (ref "IC13") (pin "55") (pinfunction "AGND8_55") (pintype "bidirectional"))
      (node (ref "IC13") (pin "56") (pinfunction "AGND9_56") (pintype "bidirectional"))
      (node (ref "IC13") (pin "58") (pinfunction "V3GND_58") (pintype "bidirectional"))
      (node (ref "IC13") (pin "60") (pinfunction "V4GND_60") (pintype "bidirectional"))
      (node (ref "IC13") (pin "61") (pinfunction "AGND10_61") (pintype "bidirectional"))
      (node (ref "IC13") (pin "62") (pinfunction "AGND11_62") (pintype "bidirectional"))
      (node (ref "IC13") (pin "63") (pinfunction "AGND12_63") (pintype "bidirectional"))
      (node (ref "IC13") (pin "64") (pinfunction "AGND13_64") (pintype "bidirectional"))
      (node (ref "IC14") (pin "1") (pinfunction "P$1_1") (pintype "bidirectional"))
      (node (ref "IC14") (pin "3") (pinfunction "P$3_3") (pintype "bidirectional"))
      (node (ref "IC15") (pin "1") (pinfunction "P$1_1") (pintype "bidirectional"))
      (node (ref "IC15") (pin "3") (pinfunction "P$3_3") (pintype "bidirectional"))
      (node (ref "IC2") (pin "P3") (pinfunction "GND_P3") (pintype "passive"))
      (node (ref "IC4") (pin "P$3") (pinfunction "GND_P$3") (pintype "bidirectional"))
      (node (ref "IC4") (pin "P$6") (pinfunction "GND_T_P$6") (pintype "bidirectional"))
      (node (ref "IC5") (pin "15") (pinfunction "GND2_15") (pintype "bidirectional"))
      (node (ref "IC5") (pin "9") (pinfunction "GND2_9") (pintype "bidirectional"))
      (node (ref "IC6") (pin "18") (pinfunction "GND_18") (pintype "power_in"))
      (node (ref "IC6") (pin "30") (pinfunction "GND_30") (pintype "power_in"))
      (node (ref "IC6") (pin "38") (pinfunction "GND_38") (pintype "power_in"))
      (node (ref "IC6") (pin "8") (pinfunction "GND_8") (pintype "power_in"))
      (node (ref "IC7") (pin "2") (pinfunction "GND_2") (pintype "bidirectional"))
      (node (ref "IC8") (pin "1") (pinfunction "P$1_1") (pintype "bidirectional"))
      (node (ref "IC8") (pin "3") (pinfunction "P$3_3") (pintype "bidirectional"))
      (node (ref "IC9") (pin "1") (pinfunction "P$1_1") (pintype "bidirectional"))
      (node (ref "IC9") (pin "3") (pinfunction "P$3_3") (pintype "bidirectional"))
      (node (ref "JACK") (pin "P2") (pinfunction "2_P2") (pintype "passive"))
      (node (ref "JACK") (pin "P3") (pinfunction "3_P3") (pintype "passive"))
      (node (ref "OSC1") (pin "P$2") (pinfunction "GND_P$2") (pintype "passive"))
      (node (ref "PDI") (pin "6") (pinfunction "6_6") (pintype "passive"))
      (node (ref "R18") (pin "1") (pinfunction "1_1") (pintype "passive"))
      (node (ref "R21") (pin "1") (pinfunction "1_1") (pintype "passive"))
      (node (ref "R23") (pin "1") (pinfunction "1_1") (pintype "passive"))
      (node (ref "R25") (pin "1") (pinfunction "1_1") (pintype "passive"))
      (node (ref "R6") (pin "1") (pinfunction "1_1") (pintype "passive"))
      (node (ref "R8") (pin "1") (pinfunction "1_1") (pintype "passive"))
      (node (ref "R9") (pin "1") (pinfunction "1_1") (pintype "passive"))
      (node (ref "RTRIM") (pin "1") (pinfunction "1_1") (pintype "passive"))
      (node (ref "STATE") (pin "K") (pinfunction "K_K") (pintype "bidirectional"))
      (node (ref "TP2") (pin "TP") (pinfunction "TP_TP") (pintype "input"))
      (node (ref "X1") (pin "P1") (pinfunction "1_P1") (pintype "passive"))
      (node (ref "X1") (pin "P6") (pinfunction "6_P6") (pintype "passive"))
      (node (ref "X1") (pin "P8") (pinfunction "8_P8") (pintype "passive"))
      (node (ref "X2") (pin "P2") (pinfunction "2_P2") (pintype "passive"))
    )
    (net (code "23") (name "GND2") (class "Default")
      (node (ref "C10") (pin "2") (pinfunction "2_2") (pintype "passive"))
      (node (ref "C11") (pin "2") (pinfunction "2_2") (pintype "passive"))
      (node (ref "C15") (pin "2") (pinfunction "2_2") (pintype "passive"))
      (node (ref "C2") (pin "2") (pinfunction "2_2") (pintype "passive"))
      (node (ref "C4") (pin "2") (pinfunction "2_2") (pintype "passive"))
      (node (ref "C5") (pin "2") (pinfunction "2_2") (pintype "passive"))
      (node (ref "C8") (pin "2") (pinfunction "2_2") (pintype "passive"))
      (node (ref "C9") (pin "-") (pinfunction "-_-") (pintype "passive"))
      (node (ref "CUSB") (pin "2") (pinfunction "2_2") (pintype "passive"))
      (node (ref "IC1") (pin "P$2") (pinfunction "GND_P$2") (pintype "bidirectional"))
      (node (ref "IC3") (pin "18") (pinfunction "GND_18") (pintype "power_in"))
      (node (ref "IC3") (pin "21") (pinfunction "GND_21") (pintype "power_in"))
      (node (ref "IC3") (pin "25") (pinfunction "GND_25") (pintype "power_in"))
      (node (ref "IC3") (pin "26") (pinfunction "TEST_26") (pintype "input"))
      (node (ref "IC3") (pin "7") (pinfunction "GND_7") (pintype "power_in"))
      (node (ref "IC5") (pin "2") (pinfunction "GND1_2") (pintype "bidirectional"))
      (node (ref "IC5") (pin "8") (pinfunction "GND1_8") (pintype "bidirectional"))
      (node (ref "RUSB") (pin "2") (pinfunction "2_2") (pintype "passive"))
      (node (ref "TP1") (pin "TP") (pinfunction "TP_TP") (pintype "input"))
      (node (ref "USB") (pin "P$5") (pinfunction "5_P$5") (pintype "bidirectional"))
    )
    (net (code "24") (name "IN00") (class "Default")
      (node (ref "IC12") (pin "4") (pinfunction "P$4_4") (pintype "bidirectional"))
      (node (ref "IC6") (pin "4") (pinfunction "PB0/ADC8/AREF_4") (pintype "bidirectional"))
    )
    (net (code "25") (name "Net-(C6-Pad+)") (class "Default")
      (node (ref "C6") (pin "+") (pinfunction "+_+") (pintype "passive"))
      (node (ref "R1") (pin "1") (pinfunction "1_1") (pintype "passive"))
    )
    (net (code "26") (name "Net-(CTUNE-Pad1)") (class "Default")
      (node (ref "CTUNE") (pin "1") (pinfunction "1_1") (pintype "passive"))
      (node (ref "RTUNE") (pin "1") (pinfunction "1_1") (pintype "passive"))
    )
    (net (code "27") (name "Net-(IC1-VBUS)") (class "Default")
      (node (ref "C2") (pin "1") (pinfunction "1_1") (pintype "passive"))
      (node (ref "IC1") (pin "P$5") (pinfunction "VBUS_P$5") (pintype "bidirectional"))
      (node (ref "L1") (pin "2") (pinfunction "2_2") (pintype "passive"))
      (node (ref "USB") (pin "P$1") (pinfunction "1_P$1") (pintype "bidirectional"))
    )
    (net (code "28") (name "Net-(IC2-ON{slash}OFF)") (class "Default")
      (node (ref "IC2") (pin "P1") (pinfunction "ON/OFF_P1") (pintype "passive"))
      (node (ref "R2") (pin "1") (pinfunction "1_1") (pintype "passive"))
    )
    (net (code "29") (name "Net-(IC2-TRIM)") (class "Default")
      (node (ref "CTUNE") (pin "2") (pinfunction "2_2") (pintype "passive"))
      (node (ref "IC2") (pin "P5") (pinfunction "TRIM_P5") (pintype "passive"))
      (node (ref "RTRIM") (pin "2") (pinfunction "2_2") (pintype "passive"))
    )
    (net (code "30") (name "Net-(IC2-VIN)") (class "Default")
      (node (ref "C7") (pin "1") (pinfunction "1_1") (pintype "passive"))
      (node (ref "IC2") (pin "P2") (pinfunction "VIN_P2") (pintype "passive"))
      (node (ref "L2") (pin "2") (pinfunction "2_2") (pintype "passive"))
      (node (ref "R1") (pin "2") (pinfunction "2_2") (pintype "passive"))
      (node (ref "R2") (pin "2") (pinfunction "2_2") (pintype "passive"))
    )
    (net (code "31") (name "Net-(IC3-3V3OUT)") (class "Default")
      (node (ref "C10") (pin "1") (pinfunction "1_1") (pintype "passive"))
      (node (ref "IC3") (pin "17") (pinfunction "3V3OUT_17") (pintype "output"))
    )
    (net (code "32") (name "Net-(IC3-CBUS0)") (class "Default")
      (node (ref "IC3") (pin "23") (pinfunction "CBUS0_23") (pintype "bidirectional"))
      (node (ref "TX1") (pin "K") (pinfunction "K_K") (pintype "bidirectional"))
    )
    (net (code "33") (name "Net-(IC3-CBUS1)") (class "Default")
      (node (ref "IC3") (pin "22") (pinfunction "CBUS1_22") (pintype "bidirectional"))
      (node (ref "RX1") (pin "K") (pinfunction "K_K") (pintype "bidirectional"))
    )
    (net (code "34") (name "Net-(IC4-NR{slash}FB)") (class "Default")
      (node (ref "C16") (pin "2") (pinfunction "2_2") (pintype "passive"))
      (node (ref "IC4") (pin "P$5") (pinfunction "NR/FB_P$5") (pintype "bidirectional"))
      (node (ref "R5") (pin "1") (pinfunction "1_1") (pintype "passive"))
      (node (ref "R6") (pin "2") (pinfunction "2_2") (pintype "passive"))
    )
    (net (code "35") (name "Net-(IC6-PR1{slash}XTAL1)") (class "Default")
      (node (ref "IC6") (pin "37") (pinfunction "PR1/XTAL1_37") (pintype "bidirectional"))
      (node (ref "OSC1") (pin "P$3") (pinfunction "OUTPUT_P$3") (pintype "passive"))
    )
    (net (code "36") (name "Net-(IC8-P$4)") (class "Default")
      (node (ref "IC8") (pin "4") (pinfunction "P$4_4") (pintype "bidirectional"))
      (node (ref "R16") (pin "1") (pinfunction "1_1") (pintype "passive"))
    )
    (net (code "37") (name "Net-(IC9-P$4)") (class "Default")
      (node (ref "IC9") (pin "4") (pinfunction "P$4_4") (pintype "bidirectional"))
      (node (ref "R11") (pin "1") (pinfunction "1_1") (pintype "passive"))
    )
    (net (code "38") (name "Net-(IC10-P$4)") (class "Default")
      (node (ref "IC10") (pin "4") (pinfunction "P$4_4") (pintype "bidirectional"))
      (node (ref "R12") (pin "1") (pinfunction "1_1") (pintype "passive"))
    )
    (net (code "39") (name "Net-(IC11-P$4)") (class "Default")
      (node (ref "IC11") (pin "4") (pinfunction "P$4_4") (pintype "bidirectional"))
      (node (ref "R17") (pin "1") (pinfunction "1_1") (pintype "passive"))
    )
    (net (code "40") (name "Net-(IC13-RANGE)") (class "Default")
      (node (ref "IC13") (pin "8") (pinfunction "RANGE_8") (pintype "bidirectional"))
      (node (ref "R10") (pin "1") (pinfunction "1_1") (pintype "passive"))
      (node (ref "R9") (pin "2") (pinfunction "2_2") (pintype "passive"))
    )
    (net (code "41") (name "Net-(IC13-REFCAPA)") (class "Default")
      (node (ref "C44") (pin "2") (pinfunction "2_2") (pintype "passive"))
      (node (ref "IC13") (pin "44") (pinfunction "REFCAPA_44") (pintype "bidirectional"))
      (node (ref "IC13") (pin "45") (pinfunction "REFCAPB_45") (pintype "bidirectional"))
    )
    (net (code "42") (name "Net-(IC13-REFIN{slash}REFOUT)") (class "Default")
      (node (ref "C45") (pin "2") (pinfunction "2_2") (pintype "passive"))
      (node (ref "IC13") (pin "42") (pinfunction "REFIN/REFOUT_42") (pintype "input"))
    )
    (net (code "43") (name "Net-(IC13-REGCAP0)") (class "Default")
      (node (ref "C47") (pin "2") (pinfunction "2_2") (pintype "passive"))
      (node (ref "IC13") (pin "36") (pinfunction "REGCAP0_36") (pintype "bidirectional"))
    )
    (net (code "44") (name "Net-(IC13-REGCAP1)") (class "Default")
      (node (ref "C46") (pin "2") (pinfunction "2_2") (pintype "passive"))
      (node (ref "IC13") (pin "39") (pinfunction "REGCAP1_39") (pintype "bidirectional"))
    )
    (net (code "45") (name "Net-(IC14-P$2)") (class "Default")
      (node (ref "C37") (pin "2") (pinfunction "2_2") (pintype "passive"))
      (node (ref "IC14") (pin "2") (pinfunction "P$2_2") (pintype "bidirectional"))
      (node (ref "R13") (pin "2") (pinfunction "2_2") (pintype "passive"))
    )
    (net (code "46") (name "Net-(IC14-P$4)") (class "Default")
      (node (ref "IC14") (pin "4") (pinfunction "P$4_4") (pintype "bidirectional"))
      (node (ref "R14") (pin "1") (pinfunction "1_1") (pintype "passive"))
    )
    (net (code "47") (name "Net-(IC15-P$2)") (class "Default")
      (node (ref "C39") (pin "2") (pinfunction "2_2") (pintype "passive"))
      (node (ref "IC15") (pin "2") (pinfunction "P$2_2") (pintype "bidirectional"))
      (node (ref "R14") (pin "2") (pinfunction "2_2") (pintype "passive"))
    )
    (net (code "48") (name "Net-(R3-Pad1)") (class "Default")
      (node (ref "R3") (pin "1") (pinfunction "1_1") (pintype "passive"))
      (node (ref "TX1") (pin "A") (pinfunction "A_A") (pintype "bidirectional"))
    )
    (net (code "49") (name "Net-(R4-Pad1)") (class "Default")
      (node (ref "R4") (pin "1") (pinfunction "1_1") (pintype "passive"))
      (node (ref "RX1") (pin "A") (pinfunction "A_A") (pintype "bidirectional"))
    )
    (net (code "50") (name "Net-(R15-Pad1)") (class "Default")
      (node (ref "R15") (pin "1") (pinfunction "1_1") (pintype "passive"))
      (node (ref "STATE") (pin "A") (pinfunction "A_A") (pintype "bidirectional"))
    )
    (net (code "51") (name "Net-(USB-2)") (class "Default")
      (node (ref "IC1") (pin "P$1") (pinfunction "IO1_P$1") (pintype "bidirectional"))
      (node (ref "USB") (pin "P$2") (pinfunction "2_P$2") (pintype "bidirectional"))
    )
    (net (code "52") (name "Net-(USB-3)") (class "Default")
      (node (ref "IC1") (pin "P$3") (pinfunction "IO2_P$3") (pintype "bidirectional"))
      (node (ref "USB") (pin "P$3") (pinfunction "3_P$3") (pintype "bidirectional"))
    )
    (net (code "53") (name "Net-(USB-P$1)") (class "Default")
      (node (ref "RUSB") (pin "1") (pinfunction "1_1") (pintype "passive"))
      (node (ref "USB") (pin "SHIELD_1") (pinfunction "P$1_SHIELD_1") (pintype "bidirectional"))
    )
    (net (code "54") (name "Net-(USB-P$4)") (class "Default")
      (node (ref "CUSB") (pin "1") (pinfunction "1_1") (pintype "passive"))
      (node (ref "USB") (pin "SHIELD_4") (pinfunction "P$4_SHIELD_4") (pintype "bidirectional"))
    )
    (net (code "55") (name "OS0") (class "Default")
      (node (ref "IC13") (pin "3") (pinfunction "OS0_3") (pintype "bidirectional"))
      (node (ref "IC6") (pin "22") (pinfunction "~OC0CRXD0PD2_22") (pintype "bidirectional"))
      (node (ref "R20") (pin "1") (pinfunction "1_1") (pintype "passive"))
      (node (ref "R21") (pin "2") (pinfunction "2_2") (pintype "passive"))
    )
    (net (code "56") (name "OS1") (class "Default")
      (node (ref "IC13") (pin "4") (pinfunction "OS1_4") (pintype "bidirectional"))
      (node (ref "IC6") (pin "23") (pinfunction "~OC0DTXD0PD3_23") (pintype "bidirectional"))
      (node (ref "R22") (pin "1") (pinfunction "1_1") (pintype "passive"))
      (node (ref "R23") (pin "2") (pinfunction "2_2") (pintype "passive"))
    )
    (net (code "57") (name "OS2") (class "Default")
      (node (ref "IC13") (pin "5") (pinfunction "OS2_5") (pintype "bidirectional"))
      (node (ref "IC6") (pin "24") (pinfunction "~{#SSPD4}_24") (pintype "bidirectional"))
      (node (ref "R24") (pin "1") (pinfunction "1_1") (pintype "passive"))
      (node (ref "R25") (pin "2") (pinfunction "2_2") (pintype "passive"))
    )
    (net (code "58") (name "OUT0") (class "Default")
      (node (ref "IC6") (pin "5") (pinfunction "PB1/ADC9_5") (pintype "bidirectional"))
      (node (ref "IC8") (pin "2") (pinfunction "P$2_2") (pintype "bidirectional"))
    )
    (net (code "59") (name "OUT1") (class "Default")
      (node (ref "IC6") (pin "40") (pinfunction "PA0/ADC0/AREF_40") (pintype "bidirectional"))
      (node (ref "IC9") (pin "2") (pinfunction "P$2_2") (pintype "bidirectional"))
    )
    (net (code "60") (name "OUT2") (class "Default")
      (node (ref "IC10") (pin "2") (pinfunction "P$2_2") (pintype "bidirectional"))
      (node (ref "IC6") (pin "41") (pinfunction "PA1/ADC1_41") (pintype "bidirectional"))
    )
    (net (code "61") (name "OUT3") (class "Default")
      (node (ref "IC11") (pin "2") (pinfunction "P$2_2") (pintype "bidirectional"))
      (node (ref "IC6") (pin "42") (pinfunction "PA2/ADC2_42") (pintype "bidirectional"))
    )
    (net (code "62") (name "P5.45V") (class "Default")
      (node (ref "C12") (pin "1") (pinfunction "1_1") (pintype "passive"))
      (node (ref "C13") (pin "1") (pinfunction "1_1") (pintype "passive"))
      (node (ref "C14") (pin "1") (pinfunction "1_1") (pintype "passive"))
      (node (ref "IC2") (pin "P4") (pinfunction "VOUT_P4") (pintype "passive"))
      (node (ref "IC4") (pin "P$1") (pinfunction "EN_P$1") (pintype "bidirectional"))
      (node (ref "IC4") (pin "P$2") (pinfunction "IN_P$2") (pintype "bidirectional"))
      (node (ref "RTUNE") (pin "2") (pinfunction "2_2") (pintype "passive"))
    )
    (net (code "63") (name "PDI-CLK") (class "Default")
      (node (ref "IC6") (pin "35") (pinfunction "RESET/PDI-CLK_35") (pintype "input"))
      (node (ref "PDI") (pin "5") (pinfunction "5_5") (pintype "passive"))
    )
    (net (code "64") (name "PDI-DATA") (class "Default")
      (node (ref "IC6") (pin "34") (pinfunction "PDI-DATA_34") (pintype "bidirectional"))
      (node (ref "PDI") (pin "1") (pinfunction "1_1") (pintype "passive"))
    )
    (net (code "65") (name "RESET") (class "Default")
      (node (ref "IC13") (pin "11") (pinfunction "RESET_11") (pintype "bidirectional"))
      (node (ref "IC15") (pin "4") (pinfunction "P$4_4") (pintype "bidirectional"))
      (node (ref "IC6") (pin "20") (pinfunction "~{OC0APD0}_20") (pintype "bidirectional"))
    )
    (net (code "66") (name "RTS") (class "Default")
      (node (ref "IC5") (pin "13") (pinfunction "B2_13") (pintype "bidirectional"))
      (node (ref "IC6") (pin "28") (pinfunction "~{OC0ASDAPE0}_28") (pintype "bidirectional"))
    )
    (net (code "67") (name "RXD") (class "Default")
      (node (ref "IC5") (pin "12") (pinfunction "B3_12") (pintype "bidirectional"))
      (node (ref "IC6") (pin "33") (pinfunction "~TXD0OC0DPE3_33") (pintype "bidirectional"))
    )
    (net (code "68") (name "SCK0") (class "Default")
      (node (ref "IC13") (pin "12") (pinfunction "~{RD}/SCLK_12") (pintype "bidirectional"))
      (node (ref "IC6") (pin "17") (pinfunction "PC7/SCK/TXD1/CLKO/EVO_17") (pintype "bidirectional"))
    )
    (net (code "69") (name "SDI") (class "Default")
      (node (ref "IC6") (pin "15") (pinfunction "PC5/OC1B/MOSI/XCK1_15") (pintype "bidirectional"))
    )
    (net (code "70") (name "SDO") (class "Default")
      (node (ref "IC13") (pin "24") (pinfunction "DB7/DOUTA_24") (pintype "bidirectional"))
      (node (ref "IC6") (pin "16") (pinfunction "PC6/MISO/RXD1_16") (pintype "bidirectional"))
    )
    (net (code "71") (name "STATE") (class "Default")
      (node (ref "IC6") (pin "36") (pinfunction "PR0/XTAL2_36") (pintype "bidirectional"))
      (node (ref "R15") (pin "2") (pinfunction "2_2") (pintype "passive"))
    )
    (net (code "72") (name "TXD") (class "Default")
      (node (ref "IC5") (pin "14") (pinfunction "B1_14") (pintype "bidirectional"))
      (node (ref "IC6") (pin "32") (pinfunction "~RXD0OC0CPE2_32") (pintype "bidirectional"))
    )
    (net (code "73") (name "USB5V") (class "Default")
      (node (ref "C11") (pin "1") (pinfunction "1_1") (pintype "passive"))
      (node (ref "C15") (pin "1") (pinfunction "1_1") (pintype "passive"))
      (node (ref "C8") (pin "1") (pinfunction "1_1") (pintype "passive"))
      (node (ref "C9") (pin "+") (pinfunction "+_+") (pintype "passive"))
      (node (ref "IC3") (pin "20") (pinfunction "VCC_20") (pintype "power_in"))
      (node (ref "IC3") (pin "4") (pinfunction "VCCIO_4") (pintype "power_in"))
      (node (ref "IC5") (pin "1") (pinfunction "VDD1_1") (pintype "bidirectional"))
      (node (ref "IC5") (pin "7") (pinfunction "NC/EN_7") (pintype "bidirectional"))
      (node (ref "L1") (pin "1") (pinfunction "1_1") (pintype "passive"))
      (node (ref "R3") (pin "2") (pinfunction "2_2") (pintype "passive"))
      (node (ref "R4") (pin "2") (pinfunction "2_2") (pintype "passive"))
    )
    (net (code "74") (name "USBDM") (class "Default")
      (node (ref "C5") (pin "1") (pinfunction "1_1") (pintype "passive"))
      (node (ref "IC1") (pin "P$6") (pinfunction "IO1_P$6") (pintype "bidirectional"))
      (node (ref "IC3") (pin "16") (pinfunction "USBDM_16") (pintype "bidirectional"))
    )
    (net (code "75") (name "USBDP") (class "Default")
      (node (ref "C4") (pin "1") (pinfunction "1_1") (pintype "passive"))
      (node (ref "IC1") (pin "P$4") (pinfunction "IO2_P$4") (pintype "bidirectional"))
      (node (ref "IC3") (pin "15") (pinfunction "USBDP_15") (pintype "bidirectional"))
    )
    (net (code "76") (name "VCCIO") (class "Default")
      (node (ref "C17") (pin "1") (pinfunction "1_1") (pintype "passive"))
      (node (ref "C19") (pin "1") (pinfunction "1_1") (pintype "passive"))
      (node (ref "C21") (pin "1") (pinfunction "1_1") (pintype "passive"))
      (node (ref "C22") (pin "1") (pinfunction "1_1") (pintype "passive"))
      (node (ref "C23") (pin "1") (pinfunction "1_1") (pintype "passive"))
      (node (ref "C24") (pin "1") (pinfunction "1_1") (pintype "passive"))
      (node (ref "C25") (pin "1") (pinfunction "1_1") (pintype "passive"))
      (node (ref "C26") (pin "1") (pinfunction "1_1") (pintype "passive"))
      (node (ref "C27") (pin "1") (pinfunction "1_1") (pintype "passive"))
      (node (ref "C34") (pin "1") (pinfunction "1_1") (pintype "passive"))
      (node (ref "C38") (pin "1") (pinfunction "1_1") (pintype "passive"))
      (node (ref "C40") (pin "1") (pinfunction "1_1") (pintype "passive"))
      (node (ref "CLKIN") (pin "1") (pinfunction "1_1") (pintype "passive"))
      (node (ref "IC12") (pin "5") (pinfunction "P$5_5") (pintype "bidirectional"))
      (node (ref "IC13") (pin "23") (pinfunction "VDRIVE_23") (pintype "bidirectional"))
      (node (ref "IC13") (pin "34") (pinfunction "REFSELECT_34") (pintype "bidirectional"))
      (node (ref "IC13") (pin "6") (pinfunction "~{PAR}/SER/BYTESEL_6") (pintype "bidirectional"))
      (node (ref "IC13") (pin "7") (pinfunction "~{STBY}_7") (pintype "bidirectional"))
      (node (ref "IC14") (pin "5") (pinfunction "P$5_5") (pintype "bidirectional"))
      (node (ref "IC15") (pin "5") (pinfunction "P$5_5") (pintype "bidirectional"))
      (node (ref "IC5") (pin "10") (pinfunction "NC/EN_10") (pintype "bidirectional"))
      (node (ref "IC5") (pin "16") (pinfunction "VDD2_16") (pintype "bidirectional"))
      (node (ref "IC6") (pin "19") (pinfunction "VCC_19") (pintype "power_in"))
      (node (ref "IC6") (pin "31") (pinfunction "VCC_31") (pintype "power_in"))
      (node (ref "IC6") (pin "39") (pinfunction "AVCC_39") (pintype "power_in"))
      (node (ref "IC6") (pin "9") (pinfunction "VCC_9") (pintype "power_in"))
      (node (ref "IC7") (pin "5") (pinfunction "OUT_5") (pintype "bidirectional"))
      (node (ref "J1") (pin "3") (pinfunction "3_3") (pintype "passive"))
      (node (ref "OSC1") (pin "P$4") (pinfunction "VDD_P$4") (pintype "passive"))
      (node (ref "PDI") (pin "2") (pinfunction "2_2") (pintype "passive"))
      (node (ref "R10") (pin "2") (pinfunction "2_2") (pintype "passive"))
      (node (ref "R13") (pin "1") (pinfunction "1_1") (pintype "passive"))
      (node (ref "R20") (pin "2") (pinfunction "2_2") (pintype "passive"))
      (node (ref "R22") (pin "2") (pinfunction "2_2") (pintype "passive"))
      (node (ref "R24") (pin "2") (pinfunction "2_2") (pintype "passive"))
      (node (ref "R7") (pin "2") (pinfunction "2_2") (pintype "passive"))
    )
    (net (code "77") (name "unconnected-(IC3-CBUS2-Pad13)") (class "Default")
      (node (ref "IC3") (pin "13") (pinfunction "CBUS2_13") (pintype "bidirectional"))
    )
    (net (code "78") (name "unconnected-(IC3-CBUS3-Pad14)") (class "Default")
      (node (ref "IC3") (pin "14") (pinfunction "CBUS3_14") (pintype "bidirectional"))
    )
    (net (code "79") (name "unconnected-(IC3-CBUS4-Pad12)") (class "Default")
      (node (ref "IC3") (pin "12") (pinfunction "CBUS4_12") (pintype "bidirectional"))
    )
    (net (code "80") (name "unconnected-(IC3-OSCI-Pad27)") (class "Default")
      (node (ref "IC3") (pin "27") (pinfunction "OSCI_27") (pintype "input"))
    )
    (net (code "81") (name "unconnected-(IC3-OSCO-Pad28)") (class "Default")
      (node (ref "IC3") (pin "28") (pinfunction "OSCO_28") (pintype "output"))
    )
    (net (code "82") (name "unconnected-(IC3-~{DCD}-Pad10)") (class "Default")
      (node (ref "IC3") (pin "10") (pinfunction "~{DCD}_10") (pintype "input"))
    )
    (net (code "83") (name "unconnected-(IC3-~{DSR}-Pad9)") (class "Default")
      (node (ref "IC3") (pin "9") (pinfunction "~{DSR}_9") (pintype "input"))
    )
    (net (code "84") (name "unconnected-(IC3-~{DTR}-Pad2)") (class "Default")
      (node (ref "IC3") (pin "2") (pinfunction "~{DTR}_2") (pintype "output"))
    )
    (net (code "85") (name "unconnected-(IC3-~{RESET}-Pad19)") (class "Default")
      (node (ref "IC3") (pin "19") (pinfunction "~{RESET}_19") (pintype "input"))
    )
    (net (code "86") (name "unconnected-(IC3-~{RI}-Pad6)") (class "Default")
      (node (ref "IC3") (pin "6") (pinfunction "~{RI}_6") (pintype "input"))
    )
    (net (code "87") (name "unconnected-(IC6-PA3{slash}ADC3-Pad43)") (class "Default")
      (node (ref "IC6") (pin "43") (pinfunction "PA3/ADC3_43") (pintype "bidirectional"))
    )
    (net (code "88") (name "unconnected-(IC6-PA4{slash}ADC4-Pad44)") (class "Default")
      (node (ref "IC6") (pin "44") (pinfunction "PA4/ADC4_44") (pintype "bidirectional"))
    )
    (net (code "89") (name "unconnected-(IC6-PA5{slash}ADC5-Pad1)") (class "Default")
      (node (ref "IC6") (pin "1") (pinfunction "PA5/ADC5_1") (pintype "bidirectional"))
    )
    (net (code "90") (name "unconnected-(IC6-PA6{slash}ADC6-Pad2)") (class "Default")
      (node (ref "IC6") (pin "2") (pinfunction "PA6/ADC6_2") (pintype "bidirectional"))
    )
    (net (code "91") (name "unconnected-(IC6-PA7{slash}ADC7{slash}AC0-OUT-Pad3)") (class "Default")
      (node (ref "IC6") (pin "3") (pinfunction "PA7/ADC7/AC0-OUT_3") (pintype "bidirectional"))
    )
    (net (code "92") (name "unconnected-(IC6-PB2{slash}ADC10{slash}DAC0-Pad6)") (class "Default")
      (node (ref "IC6") (pin "6") (pinfunction "PB2/ADC10/DAC0_6") (pintype "bidirectional"))
    )
    (net (code "93") (name "unconnected-(IC6-PB3{slash}ADC11{slash}DAC1-Pad7)") (class "Default")
      (node (ref "IC6") (pin "7") (pinfunction "PB3/ADC11/DAC1_7") (pintype "bidirectional"))
    )
    (net (code "94") (name "unconnected-(IC6-PC1{slash}OC0B{slash}XCK0{slash}SCL-Pad11)") (class "Default")
      (node (ref "IC6") (pin "11") (pinfunction "PC1/OC0B/XCK0/SCL_11") (pintype "bidirectional"))
    )
    (net (code "95") (name "unconnected-(IC6-PC3{slash}OC0D{slash}TXD0-Pad13)") (class "Default")
      (node (ref "IC6") (pin "13") (pinfunction "PC3/OC0D/TXD0_13") (pintype "bidirectional"))
    )
    (net (code "96") (name "unconnected-(IC6-~RXD1MISOPD6-Pad26)") (class "Default")
      (node (ref "IC6") (pin "26") (pinfunction "~RXD1MISOPD6_26") (pintype "bidirectional"))
    )
    (net (code "97") (name "unconnected-(IC6-~XCK1MOSIPD5-Pad25)") (class "Default")
      (node (ref "IC6") (pin "25") (pinfunction "~XCK1MOSIPD5_25") (pintype "bidirectional"))
    )
    (net (code "98") (name "unconnected-(IC6-~~{TXD1SCKCLKOPD7}-Pad27)") (class "Default")
      (node (ref "IC6") (pin "27") (pinfunction "~~{TXD1SCKCLKOPD7}_27") (pintype "bidirectional"))
    )
    (net (code "99") (name "unconnected-(IC7-N{slash}C-Pad4)") (class "Default")
      (node (ref "IC7") (pin "4") (pinfunction "N/C_4") (pintype "bidirectional"))
    )
    (net (code "100") (name "unconnected-(IC13-DB8{slash}DOUTB-Pad25)") (class "Default")
      (node (ref "IC13") (pin "25") (pinfunction "DB8/DOUTB_25") (pintype "bidirectional"))
    )
    (net (code "101") (name "unconnected-(IC13-FRSTDATA-Pad15)") (class "Default")
      (node (ref "IC13") (pin "15") (pinfunction "FRSTDATA_15") (pintype "bidirectional"))
    )
    (net (code "102") (name "unconnected-(OSC1-STANDBY#-PadP$1)") (class "Default")
      (node (ref "OSC1") (pin "P$1") (pinfunction "STANDBY#_P$1") (pintype "passive"))
    )
    (net (code "103") (name "unconnected-(PDI-Pad3)") (class "Default")
      (node (ref "PDI") (pin "3") (pinfunction "3_3") (pintype "passive"))
    )
    (net (code "104") (name "unconnected-(PDI-Pad4)") (class "Default")
      (node (ref "PDI") (pin "4") (pinfunction "4_4") (pintype "passive"))
    )
    (net (code "105") (name "unconnected-(USB-4-PadP$4)") (class "Default")
      (node (ref "USB") (pin "P$4") (pinfunction "4_P$4") (pintype "bidirectional"))
    )
    (net (code "106") (name "unconnected-(USB-P$2-PadSHIELD_2)") (class "Default")
      (node (ref "USB") (pin "SHIELD_2") (pinfunction "P$2_SHIELD_2") (pintype "bidirectional"))
    )
    (net (code "107") (name "unconnected-(USB-P$3-PadSHIELD_3)") (class "Default")
      (node (ref "USB") (pin "SHIELD_3") (pinfunction "P$3_SHIELD_3") (pintype "bidirectional"))
    )
    (net (code "108") (name "~{CS_ADC}") (class "Default")
      (node (ref "IC13") (pin "13") (pinfunction "~{CS}_13") (pintype "input"))
      (node (ref "IC6") (pin "10") (pinfunction "PC0/OC0A/SDA_10") (pintype "bidirectional"))
      (node (ref "R7") (pin "1") (pinfunction "1_1") (pintype "passive"))
      (node (ref "R8") (pin "2") (pinfunction "2_2") (pintype "passive"))
    )
  )
)
